# siren.net
KiCad netlist of a schematic drawn in EAGLE
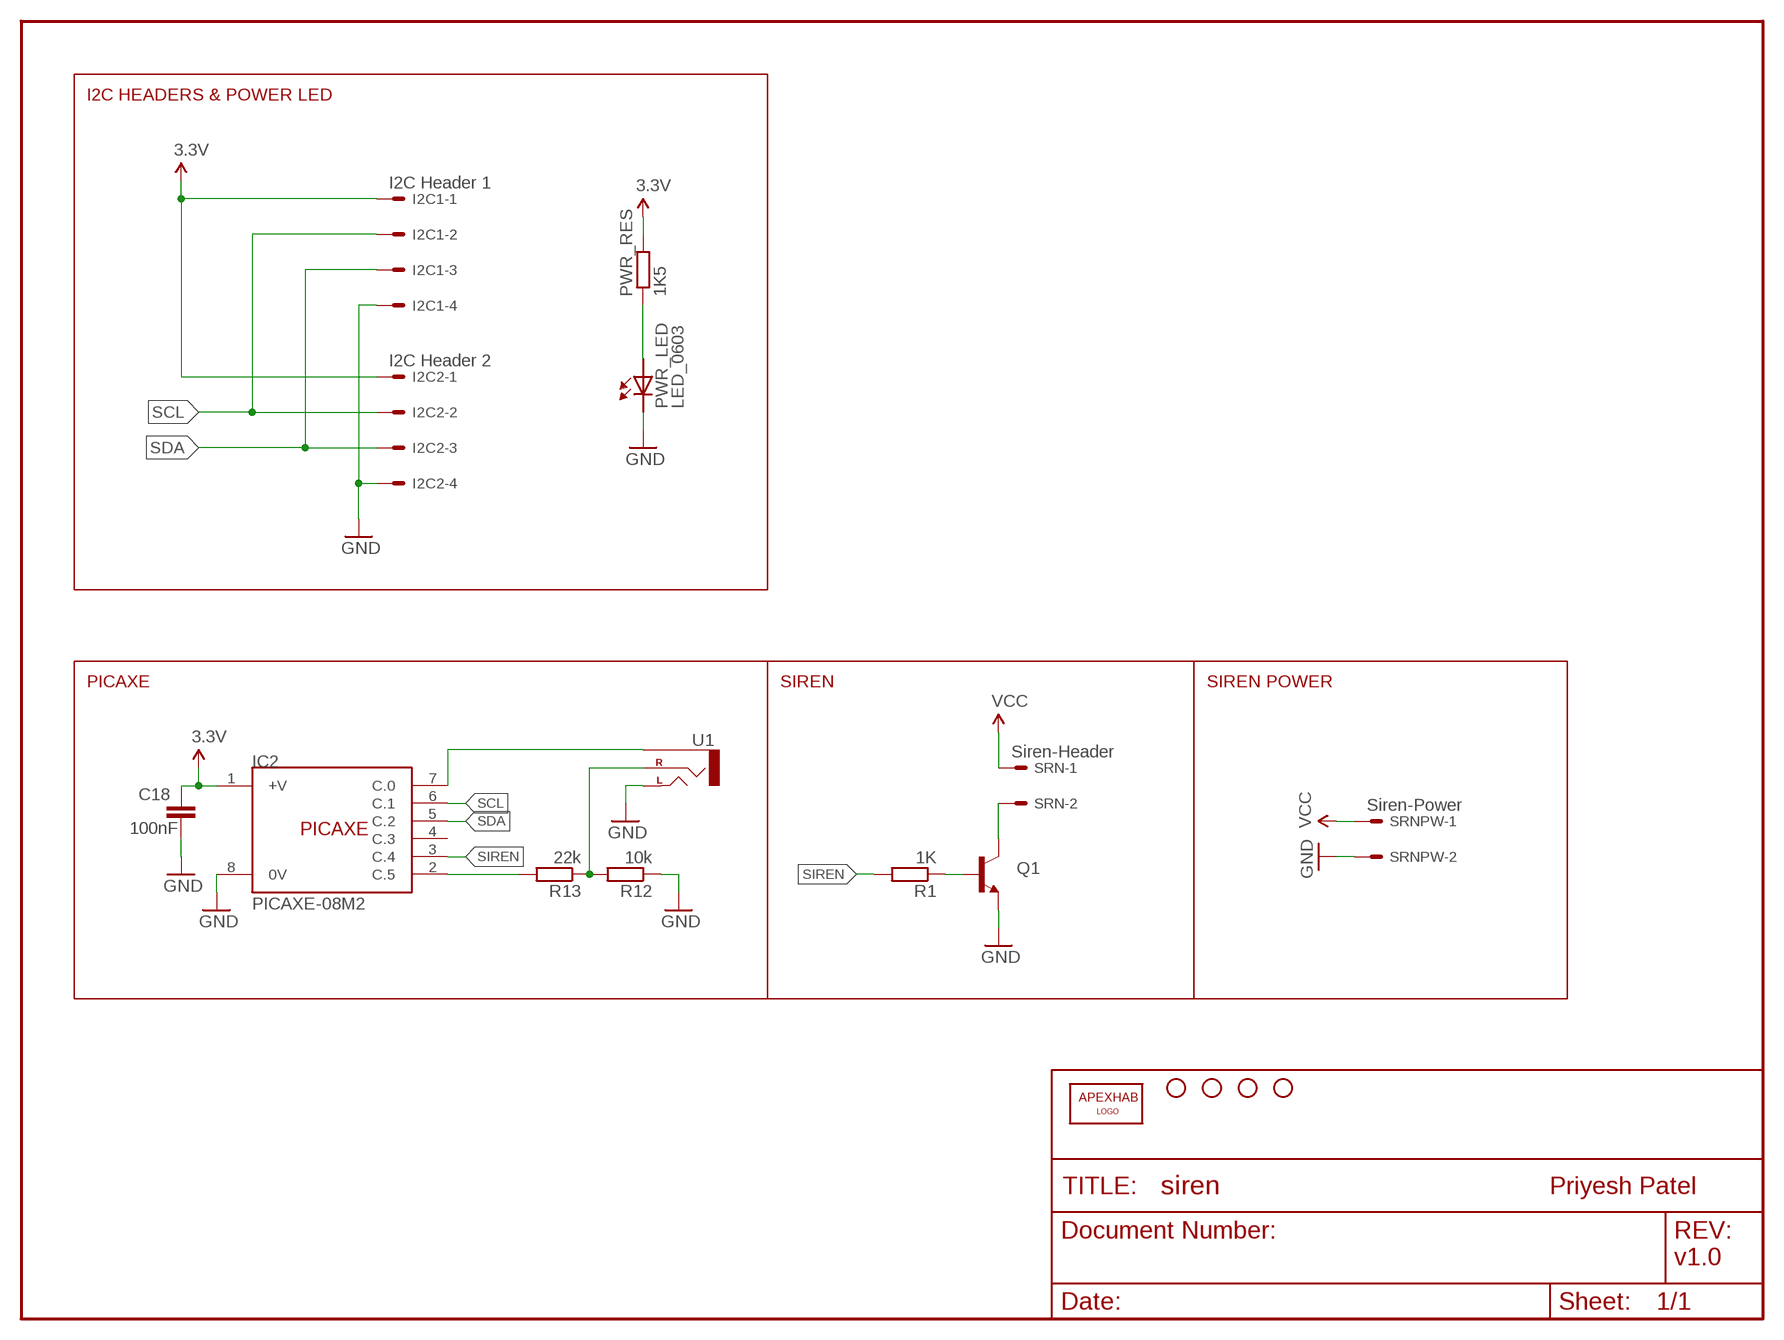
[diagram p0: schematic, sheet 1]

(export (version "E")
  (design (tool "Eeschema 10.0.6"))
  (components
    (comp (ref "C18")
      (value "100nF")
      (footprint "eagle-import:C0805")
      (libsource (lib "eagle-import") (part "C-EUC0805"))
    )
    (comp (ref "I2C1")
      (value "I2C Header 1")
      (footprint "eagle-import:6410-04")
      (libsource (lib "eagle-import") (part "22-?-0427-2041"))
    )
    (comp (ref "I2C2")
      (value "I2C Header 2")
      (footprint "eagle-import:6410-04")
      (libsource (lib "eagle-import") (part "22-?-0427-2041"))
    )
    (comp (ref "IC2")
      (value "PICAXE-08M2")
      (footprint "eagle-import:SOIC8")
      (libsource (lib "eagle-import") (part "PICAXE-08M2"))
    )
    (comp (ref "JP1")
      (value "APEXHAB-LOGO_APEXHAB-SMALL")
      (footprint "eagle-import:APEXHAB-LOGO-SMALL")
      (libsource (lib "eagle-import") (part "APEXHAB-LOGO_APEXHAB-SMALL"))
    )
    (comp (ref "JP2")
      (value "STAND-OFF")
      (footprint "eagle-import:STAND-OFF")
      (libsource (lib "eagle-import") (part "STAND-OFF"))
    )
    (comp (ref "JP3")
      (value "STAND-OFF")
      (footprint "eagle-import:STAND-OFF")
      (libsource (lib "eagle-import") (part "STAND-OFF"))
    )
    (comp (ref "JP4")
      (value "STAND-OFF")
      (footprint "eagle-import:STAND-OFF")
      (libsource (lib "eagle-import") (part "STAND-OFF"))
    )
    (comp (ref "JP5")
      (value "STAND-OFF")
      (footprint "eagle-import:STAND-OFF")
      (libsource (lib "eagle-import") (part "STAND-OFF"))
    )
    (comp (ref "PWR_LED")
      (value "LED_0603")
      (footprint "eagle-import:CHIPLED_0603")
      (libsource (lib "eagle-import") (part "LED_0603"))
    )
    (comp (ref "PWR_RES")
      (value "1K5")
      (footprint "eagle-import:R0805")
      (libsource (lib "eagle-import") (part "R-EU_R0805"))
    )
    (comp (ref "Q1")
      (value "TRANSISTOR_NPN\"")
      (footprint "eagle-import:SOT223")
      (libsource (lib "eagle-import") (part "TRANSISTOR_NPN{dblquote}"))
    )
    (comp (ref "R1")
      (value "1K")
      (footprint "eagle-import:R0805")
      (libsource (lib "eagle-import") (part "R-EU_R0805"))
    )
    (comp (ref "R12")
      (value "10k")
      (footprint "eagle-import:R0805")
      (libsource (lib "eagle-import") (part "R-EU_R0805"))
    )
    (comp (ref "R13")
      (value "22k")
      (footprint "eagle-import:R0805")
      (libsource (lib "eagle-import") (part "R-EU_R0805"))
    )
    (comp (ref "SRN")
      (value "Siren-Header")
      (footprint "eagle-import:6410-02")
      (libsource (lib "eagle-import") (part "22-?-0227-2021"))
    )
    (comp (ref "SRNPW")
      (value "Siren-Power")
      (footprint "eagle-import:6410-02")
      (libsource (lib "eagle-import") (part "22-?-0227-2021"))
    )
    (comp (ref "U1")
      (value "AUDIO-JACKPTH")
      (footprint "eagle-import:AUDIO-JACK")
      (libsource (lib "eagle-import") (part "AUDIO-JACKPTH"))
    )
  )
  (nets
    (net (code "1") (name "3.3V") (class "Default")
      (node (ref "C18") (pin "1") (pinfunction "1_1") (pintype "passive"))
      (node (ref "I2C1") (pin "1") (pinfunction "S_1") (pintype "passive"))
      (node (ref "I2C2") (pin "1") (pinfunction "S_1") (pintype "passive"))
      (node (ref "IC2") (pin "1") (pinfunction "+V_1") (pintype "power_in"))
      (node (ref "PWR_RES") (pin "2") (pinfunction "2_2") (pintype "passive"))
    )
    (net (code "2") (name "GND") (class "Default")
      (node (ref "C18") (pin "2") (pinfunction "2_2") (pintype "passive"))
      (node (ref "I2C1") (pin "4") (pinfunction "S_4") (pintype "passive"))
      (node (ref "I2C2") (pin "4") (pinfunction "S_4") (pintype "passive"))
      (node (ref "IC2") (pin "8") (pinfunction "0V_8") (pintype "power_in"))
      (node (ref "PWR_LED") (pin "C") (pinfunction "C_C") (pintype "passive"))
      (node (ref "Q1") (pin "3") (pinfunction "E_3") (pintype "passive"))
      (node (ref "R12") (pin "1") (pinfunction "1_1") (pintype "passive"))
      (node (ref "SRNPW") (pin "2") (pinfunction "S_2") (pintype "passive"))
      (node (ref "U1") (pin "TIP") (pinfunction "LEFT_TIP") (pintype "bidirectional"))
    )
    (net (code "3") (name "Net-(IC2-C.0)") (class "Default")
      (node (ref "IC2") (pin "7") (pinfunction "C.0_7") (pintype "bidirectional"))
      (node (ref "U1") (pin "SLEEVE") (pinfunction "SLEEVE_SLEEVE") (pintype "bidirectional"))
    )
    (net (code "4") (name "Net-(IC2-C.5)") (class "Default")
      (node (ref "IC2") (pin "2") (pinfunction "C.5_2") (pintype "bidirectional"))
      (node (ref "R13") (pin "2") (pinfunction "2_2") (pintype "passive"))
    )
    (net (code "5") (name "Net-(PWR_LED-PadA)") (class "Default")
      (node (ref "PWR_LED") (pin "A") (pinfunction "A_A") (pintype "passive"))
      (node (ref "PWR_RES") (pin "1") (pinfunction "1_1") (pintype "passive"))
    )
    (net (code "6") (name "Net-(Q1-B)") (class "Default")
      (node (ref "Q1") (pin "1") (pinfunction "B_1") (pintype "passive"))
      (node (ref "R1") (pin "1") (pinfunction "1_1") (pintype "passive"))
    )
    (net (code "7") (name "Net-(Q1-C)") (class "Default")
      (node (ref "Q1") (pin "2") (pinfunction "C_2") (pintype "passive"))
      (node (ref "SRN") (pin "2") (pinfunction "S_2") (pintype "passive"))
    )
    (net (code "8") (name "Net-(U1-RIGHT)") (class "Default")
      (node (ref "R12") (pin "2") (pinfunction "2_2") (pintype "passive"))
      (node (ref "R13") (pin "1") (pinfunction "1_1") (pintype "passive"))
      (node (ref "U1") (pin "RING") (pinfunction "RIGHT_RING") (pintype "bidirectional"))
    )
    (net (code "9") (name "SCL") (class "Default")
      (node (ref "I2C1") (pin "2") (pinfunction "S_2") (pintype "passive"))
      (node (ref "I2C2") (pin "2") (pinfunction "S_2") (pintype "passive"))
      (node (ref "IC2") (pin "6") (pinfunction "C.1_6") (pintype "bidirectional"))
    )
    (net (code "10") (name "SDA") (class "Default")
      (node (ref "I2C1") (pin "3") (pinfunction "S_3") (pintype "passive"))
      (node (ref "I2C2") (pin "3") (pinfunction "S_3") (pintype "passive"))
      (node (ref "IC2") (pin "5") (pinfunction "C.2_5") (pintype "bidirectional"))
    )
    (net (code "11") (name "SIREN") (class "Default")
      (node (ref "IC2") (pin "3") (pinfunction "C.4_3") (pintype "bidirectional"))
      (node (ref "R1") (pin "2") (pinfunction "2_2") (pintype "passive"))
    )
    (net (code "12") (name "VCC") (class "Default")
      (node (ref "SRN") (pin "1") (pinfunction "S_1") (pintype "passive"))
      (node (ref "SRNPW") (pin "1") (pinfunction "S_1") (pintype "passive"))
    )
    (net (code "13") (name "unconnected-(IC2-C.3-Pad4)") (class "Default")
      (node (ref "IC2") (pin "4") (pinfunction "C.3_4") (pintype "bidirectional"))
    )
  )
)
